# equaliser_TDA7418.net
KiCad netlist of a schematic drawn in EAGLE
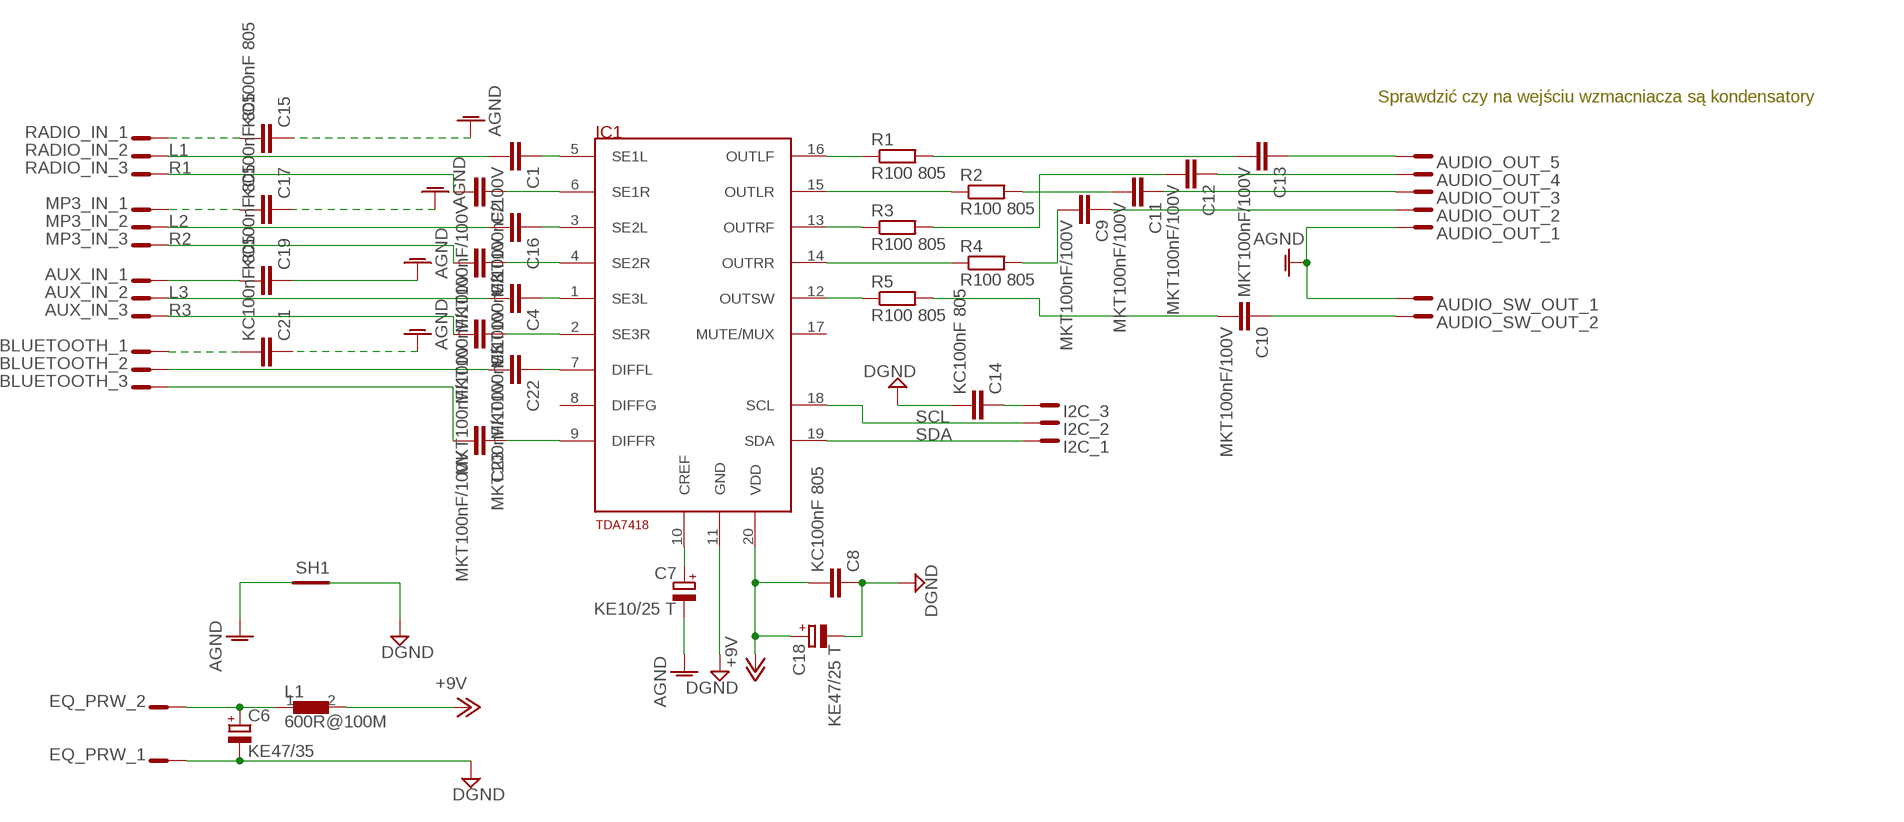
[diagram p0: schematic, sheet 1]

(export (version "E")
  (design (tool "Eeschema 10.0.6"))
  (components
    (comp (ref "AUDIO_OUT")
      (value "JST_5_PIN_B5B-PH-KS")
      (footprint "eagle-import:B5B-PH-KS")
      (libsource (lib "eagle-import") (part "JST_5_PIN_B5B-PH-KS"))
    )
    (comp (ref "AUDIO_SW_OUT")
      (value "JST_2_PIN_B2B-PH-KS")
      (footprint "eagle-import:B2B-PH-KS")
      (libsource (lib "eagle-import") (part "JST_2_PIN_B2B-PH-KS"))
    )
    (comp (ref "AUX_IN")
      (value "JST_3_PIN_B3B-PH-KS")
      (footprint "eagle-import:B3B-PH-KS")
      (libsource (lib "eagle-import") (part "JST_3_PIN_B3B-PH-KS"))
    )
    (comp (ref "BLUETOOTH")
      (value "JST_3_PIN_B3B-PH-KS")
      (footprint "eagle-import:B3B-PH-KS")
      (libsource (lib "eagle-import") (part "JST_3_PIN_B3B-PH-KS"))
    )
    (comp (ref "C1")
      (value "MKT100nF/100V")
      (footprint "eagle-import:C050-035X075")
      (libsource (lib "eagle-import") (part "C-EU050-035X075"))
    )
    (comp (ref "C2")
      (value "MKT100nF/100V")
      (footprint "eagle-import:C050-035X075")
      (libsource (lib "eagle-import") (part "C-EU050-035X075"))
    )
    (comp (ref "C3")
      (value "MKT100nF/100V")
      (footprint "eagle-import:C050-035X075")
      (libsource (lib "eagle-import") (part "C-EU050-035X075"))
    )
    (comp (ref "C4")
      (value "MKT100nF/100V")
      (footprint "eagle-import:C050-035X075")
      (libsource (lib "eagle-import") (part "C-EU050-035X075"))
    )
    (comp (ref "C5")
      (value "MKT100nF/100V")
      (footprint "eagle-import:C050-035X075")
      (libsource (lib "eagle-import") (part "C-EU050-035X075"))
    )
    (comp (ref "C6")
      (value "KE47/35")
      (footprint "eagle-import:TT2D6")
      (libsource (lib "eagle-import") (part "CPOL-EUTT2D6"))
    )
    (comp (ref "C7")
      (value "KE10/25 T")
      (footprint "eagle-import:E1,8-4")
      (libsource (lib "eagle-import") (part "resistor_CPOL-EUE1.8-4"))
    )
    (comp (ref "C8")
      (value "KC100nF 805")
      (footprint "eagle-import:C0805")
      (libsource (lib "eagle-import") (part "C-EUC0805"))
    )
    (comp (ref "C9")
      (value "MKT100nF/100V")
      (footprint "eagle-import:C050-035X075")
      (libsource (lib "eagle-import") (part "C-EU050-035X075"))
    )
    (comp (ref "C10")
      (value "MKT100nF/100V")
      (footprint "eagle-import:C050-035X075")
      (libsource (lib "eagle-import") (part "C-EU050-035X075"))
    )
    (comp (ref "C11")
      (value "MKT100nF/100V")
      (footprint "eagle-import:C050-035X075")
      (libsource (lib "eagle-import") (part "C-EU050-035X075"))
    )
    (comp (ref "C12")
      (value "MKT100nF/100V")
      (footprint "eagle-import:C050-035X075")
      (libsource (lib "eagle-import") (part "C-EU050-035X075"))
    )
    (comp (ref "C13")
      (value "MKT100nF/100V")
      (footprint "eagle-import:C050-035X075")
      (libsource (lib "eagle-import") (part "C-EU050-035X075"))
    )
    (comp (ref "C14")
      (value "KC100nF 805")
      (footprint "eagle-import:C0805")
      (libsource (lib "eagle-import") (part "C-EUC0805"))
    )
    (comp (ref "C15")
      (value "KC100nF 805")
      (footprint "eagle-import:C0805")
      (libsource (lib "eagle-import") (part "C-EUC0805"))
    )
    (comp (ref "C16")
      (value "MKT100nF/100V")
      (footprint "eagle-import:C050-035X075")
      (libsource (lib "eagle-import") (part "C-EU050-035X075"))
    )
    (comp (ref "C17")
      (value "KC100nF 805")
      (footprint "eagle-import:C0805")
      (libsource (lib "eagle-import") (part "C-EUC0805"))
    )
    (comp (ref "C18")
      (value "KE47/25 T")
      (footprint "eagle-import:B45181B")
      (libsource (lib "eagle-import") (part "CPOL-EUB45181B"))
    )
    (comp (ref "C19")
      (value "KC100nF 805")
      (footprint "eagle-import:C0805")
      (libsource (lib "eagle-import") (part "C-EUC0805"))
    )
    (comp (ref "C21")
      (value "KC100nF 805")
      (footprint "eagle-import:C0805")
      (libsource (lib "eagle-import") (part "C-EUC0805"))
    )
    (comp (ref "C22")
      (value "MKT100nF/100V")
      (footprint "eagle-import:C050-035X075")
      (libsource (lib "eagle-import") (part "C-EU050-035X075"))
    )
    (comp (ref "C23")
      (value "MKT100nF/100V")
      (footprint "eagle-import:C050-035X075")
      (libsource (lib "eagle-import") (part "C-EU050-035X075"))
    )
    (comp (ref "EQ_PRW")
      (value "JST_2_PIN_B2B-XH-A")
      (footprint "eagle-import:B2B-XH-A")
      (libsource (lib "eagle-import") (part "JST_2_PIN_B2B-XH-A"))
    )
    (comp (ref "I2C")
      (value "JST_3_PIN_B3B-PH-KS")
      (footprint "eagle-import:B3B-PH-KS")
      (libsource (lib "eagle-import") (part "JST_3_PIN_B3B-PH-KS"))
    )
    (comp (ref "IC1")
      (value "TDA7418")
      (footprint "eagle-import:SO20")
      (libsource (lib "eagle-import") (part "TDA7418"))
    )
    (comp (ref "L1")
      (value "600R@100M")
      (footprint "eagle-import:R0805")
      (libsource (lib "eagle-import") (part "FERRITR0805"))
    )
    (comp (ref "MP3_IN")
      (value "JST_3_PIN_B3B-PH-KS")
      (footprint "eagle-import:B3B-PH-KS")
      (libsource (lib "eagle-import") (part "JST_3_PIN_B3B-PH-KS"))
    )
    (comp (ref "R1")
      (value "R100 805")
      (footprint "eagle-import:R0805")
      (libsource (lib "eagle-import") (part "R-EU_R0805"))
    )
    (comp (ref "R2")
      (value "R100 805")
      (footprint "eagle-import:R0805")
      (libsource (lib "eagle-import") (part "R-EU_R0805"))
    )
    (comp (ref "R3")
      (value "R100 805")
      (footprint "eagle-import:M0805")
      (libsource (lib "eagle-import") (part "R-EU_M0805"))
    )
    (comp (ref "R4")
      (value "R100 805")
      (footprint "eagle-import:M0805")
      (libsource (lib "eagle-import") (part "R-EU_M0805"))
    )
    (comp (ref "R5")
      (value "R100 805")
      (footprint "eagle-import:R0805")
      (libsource (lib "eagle-import") (part "R-EU_R0805"))
    )
    (comp (ref "RADIO_IN")
      (value "JST_3_PIN_B3B-PH-KS")
      (footprint "eagle-import:B3B-PH-KS")
      (libsource (lib "eagle-import") (part "JST_3_PIN_B3B-PH-KS"))
    )
    (comp (ref "SH1")
      (value "SHORT-HT5")
      (footprint "eagle-import:SHORT_TOP-50")
      (libsource (lib "eagle-import") (part "SHORT-HT5"))
    )
  )
  (nets
    (net (code "1") (name "+9V") (class "Default")
      (node (ref "C18") (pin "+") (pinfunction "+_+") (pintype "passive"))
      (node (ref "C8") (pin "2") (pinfunction "2_2") (pintype "passive"))
      (node (ref "IC1") (pin "20") (pinfunction "VDD_20") (pintype "bidirectional"))
      (node (ref "L1") (pin "2") (pinfunction "2_2") (pintype "passive"))
    )
    (net (code "2") (name "/L1") (class "Default")
      (node (ref "C1") (pin "2") (pinfunction "2_2") (pintype "passive"))
      (node (ref "RADIO_IN") (pin "P$2") (pinfunction "P$1_P$2") (pintype "bidirectional"))
    )
    (net (code "3") (name "/L2") (class "Default")
      (node (ref "C16") (pin "2") (pinfunction "2_2") (pintype "passive"))
      (node (ref "MP3_IN") (pin "P$2") (pinfunction "P$1_P$2") (pintype "bidirectional"))
    )
    (net (code "4") (name "/L3") (class "Default")
      (node (ref "AUX_IN") (pin "P$2") (pinfunction "P$1_P$2") (pintype "bidirectional"))
      (node (ref "C4") (pin "2") (pinfunction "2_2") (pintype "passive"))
    )
    (net (code "5") (name "/R1") (class "Default")
      (node (ref "C2") (pin "2") (pinfunction "2_2") (pintype "passive"))
      (node (ref "RADIO_IN") (pin "P$3") (pinfunction "P$1_P$3") (pintype "bidirectional"))
    )
    (net (code "6") (name "/R2") (class "Default")
      (node (ref "C3") (pin "2") (pinfunction "2_2") (pintype "passive"))
      (node (ref "MP3_IN") (pin "P$3") (pinfunction "P$1_P$3") (pintype "bidirectional"))
    )
    (net (code "7") (name "/R3") (class "Default")
      (node (ref "AUX_IN") (pin "P$3") (pinfunction "P$1_P$3") (pintype "bidirectional"))
      (node (ref "C5") (pin "2") (pinfunction "2_2") (pintype "passive"))
    )
    (net (code "8") (name "/SCL") (class "Default")
      (node (ref "I2C") (pin "P$2") (pinfunction "P$1_P$2") (pintype "bidirectional"))
      (node (ref "IC1") (pin "18") (pinfunction "SCL_18") (pintype "bidirectional"))
    )
    (net (code "9") (name "/SDA") (class "Default")
      (node (ref "I2C") (pin "P$1") (pinfunction "P$1_P$1") (pintype "bidirectional"))
      (node (ref "IC1") (pin "19") (pinfunction "SDA_19") (pintype "bidirectional"))
    )
    (net (code "10") (name "AGND") (class "Default")
      (node (ref "AUDIO_OUT") (pin "P$1") (pinfunction "P$1_P$1") (pintype "bidirectional"))
      (node (ref "AUDIO_SW_OUT") (pin "P$1") (pinfunction "P$1_P$1") (pintype "bidirectional"))
      (node (ref "C15") (pin "1") (pinfunction "1_1") (pintype "passive"))
      (node (ref "C17") (pin "1") (pinfunction "1_1") (pintype "passive"))
      (node (ref "C19") (pin "1") (pinfunction "1_1") (pintype "passive"))
      (node (ref "C21") (pin "1") (pinfunction "1_1") (pintype "passive"))
      (node (ref "C7") (pin "-") (pinfunction "-_-") (pintype "passive"))
      (node (ref "SH1") (pin "1") (pinfunction "P$1_1") (pintype "bidirectional"))
    )
    (net (code "11") (name "DGND") (class "Default")
      (node (ref "C14") (pin "2") (pinfunction "2_2") (pintype "passive"))
      (node (ref "C18") (pin "-") (pinfunction "-_-") (pintype "passive"))
      (node (ref "C6") (pin "-") (pinfunction "-_-") (pintype "passive"))
      (node (ref "C8") (pin "1") (pinfunction "1_1") (pintype "passive"))
      (node (ref "EQ_PRW") (pin "P$1") (pinfunction "P$1_P$1") (pintype "bidirectional"))
      (node (ref "IC1") (pin "11") (pinfunction "GND_11") (pintype "bidirectional"))
      (node (ref "SH1") (pin "2") (pinfunction "P$2_2") (pintype "bidirectional"))
    )
    (net (code "12") (name "Net-(AUDIO_OUTB-P$1)") (class "Default")
      (node (ref "AUDIO_OUT") (pin "P$2") (pinfunction "P$1_P$2") (pintype "bidirectional"))
      (node (ref "C9") (pin "1") (pinfunction "1_1") (pintype "passive"))
    )
    (net (code "13") (name "Net-(AUDIO_OUTC-P$1)") (class "Default")
      (node (ref "AUDIO_OUT") (pin "P$3") (pinfunction "P$1_P$3") (pintype "bidirectional"))
      (node (ref "C11") (pin "1") (pinfunction "1_1") (pintype "passive"))
    )
    (net (code "14") (name "Net-(AUDIO_OUTD-P$1)") (class "Default")
      (node (ref "AUDIO_OUT") (pin "P$4") (pinfunction "P$1_P$4") (pintype "bidirectional"))
      (node (ref "C12") (pin "1") (pinfunction "1_1") (pintype "passive"))
    )
    (net (code "15") (name "Net-(AUDIO_OUTE-P$1)") (class "Default")
      (node (ref "AUDIO_OUT") (pin "P$5") (pinfunction "P$1_P$5") (pintype "bidirectional"))
      (node (ref "C13") (pin "1") (pinfunction "1_1") (pintype "passive"))
    )
    (net (code "16") (name "Net-(AUDIO_SW_OUTB-P$1)") (class "Default")
      (node (ref "AUDIO_SW_OUT") (pin "P$2") (pinfunction "P$1_P$2") (pintype "bidirectional"))
      (node (ref "C10") (pin "1") (pinfunction "1_1") (pintype "passive"))
    )
    (net (code "17") (name "Net-(AUX_IN-PadP$1)") (class "Default")
      (node (ref "AUX_IN") (pin "P$1") (pinfunction "P$1_P$1") (pintype "bidirectional"))
      (node (ref "C19") (pin "2") (pinfunction "2_2") (pintype "passive"))
    )
    (net (code "18") (name "Net-(BLUETOOTH-PadP$1)") (class "Default")
      (node (ref "BLUETOOTH") (pin "P$1") (pinfunction "P$1_P$1") (pintype "bidirectional"))
      (node (ref "C21") (pin "2") (pinfunction "2_2") (pintype "passive"))
    )
    (net (code "19") (name "Net-(BLUETOOTHB-P$1)") (class "Default")
      (node (ref "BLUETOOTH") (pin "P$2") (pinfunction "P$1_P$2") (pintype "bidirectional"))
      (node (ref "C22") (pin "2") (pinfunction "2_2") (pintype "passive"))
    )
    (net (code "20") (name "Net-(BLUETOOTHC-P$1)") (class "Default")
      (node (ref "BLUETOOTH") (pin "P$3") (pinfunction "P$1_P$3") (pintype "bidirectional"))
      (node (ref "C23") (pin "2") (pinfunction "2_2") (pintype "passive"))
    )
    (net (code "21") (name "Net-(C9-Pad2)") (class "Default")
      (node (ref "C9") (pin "2") (pinfunction "2_2") (pintype "passive"))
      (node (ref "R4") (pin "2") (pinfunction "2_2") (pintype "passive"))
    )
    (net (code "22") (name "Net-(C10-Pad2)") (class "Default")
      (node (ref "C10") (pin "2") (pinfunction "2_2") (pintype "passive"))
      (node (ref "R5") (pin "2") (pinfunction "2_2") (pintype "passive"))
    )
    (net (code "23") (name "Net-(C11-Pad2)") (class "Default")
      (node (ref "C11") (pin "2") (pinfunction "2_2") (pintype "passive"))
      (node (ref "R2") (pin "2") (pinfunction "2_2") (pintype "passive"))
    )
    (net (code "24") (name "Net-(C12-Pad2)") (class "Default")
      (node (ref "C12") (pin "2") (pinfunction "2_2") (pintype "passive"))
      (node (ref "R3") (pin "2") (pinfunction "2_2") (pintype "passive"))
    )
    (net (code "25") (name "Net-(C13-Pad2)") (class "Default")
      (node (ref "C13") (pin "2") (pinfunction "2_2") (pintype "passive"))
      (node (ref "R1") (pin "2") (pinfunction "2_2") (pintype "passive"))
    )
    (net (code "26") (name "Net-(C15-Pad2)") (class "Default")
      (node (ref "C15") (pin "2") (pinfunction "2_2") (pintype "passive"))
      (node (ref "RADIO_IN") (pin "P$1") (pinfunction "P$1_P$1") (pintype "bidirectional"))
    )
    (net (code "27") (name "Net-(C17-Pad2)") (class "Default")
      (node (ref "C17") (pin "2") (pinfunction "2_2") (pintype "passive"))
      (node (ref "MP3_IN") (pin "P$1") (pinfunction "P$1_P$1") (pintype "bidirectional"))
    )
    (net (code "28") (name "Net-(EQ_PRWB-P$1)") (class "Default")
      (node (ref "C6") (pin "+") (pinfunction "+_+") (pintype "passive"))
      (node (ref "EQ_PRW") (pin "P$2") (pinfunction "P$1_P$2") (pintype "bidirectional"))
      (node (ref "L1") (pin "1") (pinfunction "1_1") (pintype "passive"))
    )
    (net (code "29") (name "Net-(I2CC-P$1)") (class "Default")
      (node (ref "C14") (pin "1") (pinfunction "1_1") (pintype "passive"))
      (node (ref "I2C") (pin "P$3") (pinfunction "P$1_P$3") (pintype "bidirectional"))
    )
    (net (code "30") (name "Net-(IC1-CREF)") (class "Default")
      (node (ref "C7") (pin "+") (pinfunction "+_+") (pintype "passive"))
      (node (ref "IC1") (pin "10") (pinfunction "CREF_10") (pintype "bidirectional"))
    )
    (net (code "31") (name "Net-(IC1-DIFFL)") (class "Default")
      (node (ref "C22") (pin "1") (pinfunction "1_1") (pintype "passive"))
      (node (ref "IC1") (pin "7") (pinfunction "DIFFL_7") (pintype "bidirectional"))
    )
    (net (code "32") (name "Net-(IC1-DIFFR)") (class "Default")
      (node (ref "C23") (pin "1") (pinfunction "1_1") (pintype "passive"))
      (node (ref "IC1") (pin "9") (pinfunction "DIFFR_9") (pintype "bidirectional"))
    )
    (net (code "33") (name "Net-(IC1-OUTLF)") (class "Default")
      (node (ref "IC1") (pin "16") (pinfunction "OUTLF_16") (pintype "bidirectional"))
      (node (ref "R1") (pin "1") (pinfunction "1_1") (pintype "passive"))
    )
    (net (code "34") (name "Net-(IC1-OUTLR)") (class "Default")
      (node (ref "IC1") (pin "15") (pinfunction "OUTLR_15") (pintype "bidirectional"))
      (node (ref "R2") (pin "1") (pinfunction "1_1") (pintype "passive"))
    )
    (net (code "35") (name "Net-(IC1-OUTRF)") (class "Default")
      (node (ref "IC1") (pin "13") (pinfunction "OUTRF_13") (pintype "bidirectional"))
      (node (ref "R3") (pin "1") (pinfunction "1_1") (pintype "passive"))
    )
    (net (code "36") (name "Net-(IC1-OUTRR)") (class "Default")
      (node (ref "IC1") (pin "14") (pinfunction "OUTRR_14") (pintype "bidirectional"))
      (node (ref "R4") (pin "1") (pinfunction "1_1") (pintype "passive"))
    )
    (net (code "37") (name "Net-(IC1-OUTSW)") (class "Default")
      (node (ref "IC1") (pin "12") (pinfunction "OUTSW_12") (pintype "bidirectional"))
      (node (ref "R5") (pin "1") (pinfunction "1_1") (pintype "passive"))
    )
    (net (code "38") (name "Net-(IC1-SE1L)") (class "Default")
      (node (ref "C1") (pin "1") (pinfunction "1_1") (pintype "passive"))
      (node (ref "IC1") (pin "5") (pinfunction "SE1L_5") (pintype "bidirectional"))
    )
    (net (code "39") (name "Net-(IC1-SE1R)") (class "Default")
      (node (ref "C2") (pin "1") (pinfunction "1_1") (pintype "passive"))
      (node (ref "IC1") (pin "6") (pinfunction "SE1R_6") (pintype "bidirectional"))
    )
    (net (code "40") (name "Net-(IC1-SE2L)") (class "Default")
      (node (ref "C16") (pin "1") (pinfunction "1_1") (pintype "passive"))
      (node (ref "IC1") (pin "3") (pinfunction "SE2L_3") (pintype "bidirectional"))
    )
    (net (code "41") (name "Net-(IC1-SE2R)") (class "Default")
      (node (ref "C3") (pin "1") (pinfunction "1_1") (pintype "passive"))
      (node (ref "IC1") (pin "4") (pinfunction "SE2R_4") (pintype "bidirectional"))
    )
    (net (code "42") (name "Net-(IC1-SE3L)") (class "Default")
      (node (ref "C4") (pin "1") (pinfunction "1_1") (pintype "passive"))
      (node (ref "IC1") (pin "1") (pinfunction "SE3L_1") (pintype "bidirectional"))
    )
    (net (code "43") (name "Net-(IC1-SE3R)") (class "Default")
      (node (ref "C5") (pin "1") (pinfunction "1_1") (pintype "passive"))
      (node (ref "IC1") (pin "2") (pinfunction "SE3R_2") (pintype "bidirectional"))
    )
    (net (code "44") (name "unconnected-(IC1-DIFFG-Pad8)") (class "Default")
      (node (ref "IC1") (pin "8") (pinfunction "DIFFG_8") (pintype "bidirectional"))
    )
    (net (code "45") (name "unconnected-(IC1-MUTE{slash}MUX-Pad17)") (class "Default")
      (node (ref "IC1") (pin "17") (pinfunction "MUTE/MUX_17") (pintype "bidirectional"))
    )
  )
)
